# nucleum.net
KiCad netlist of a schematic drawn in EAGLE
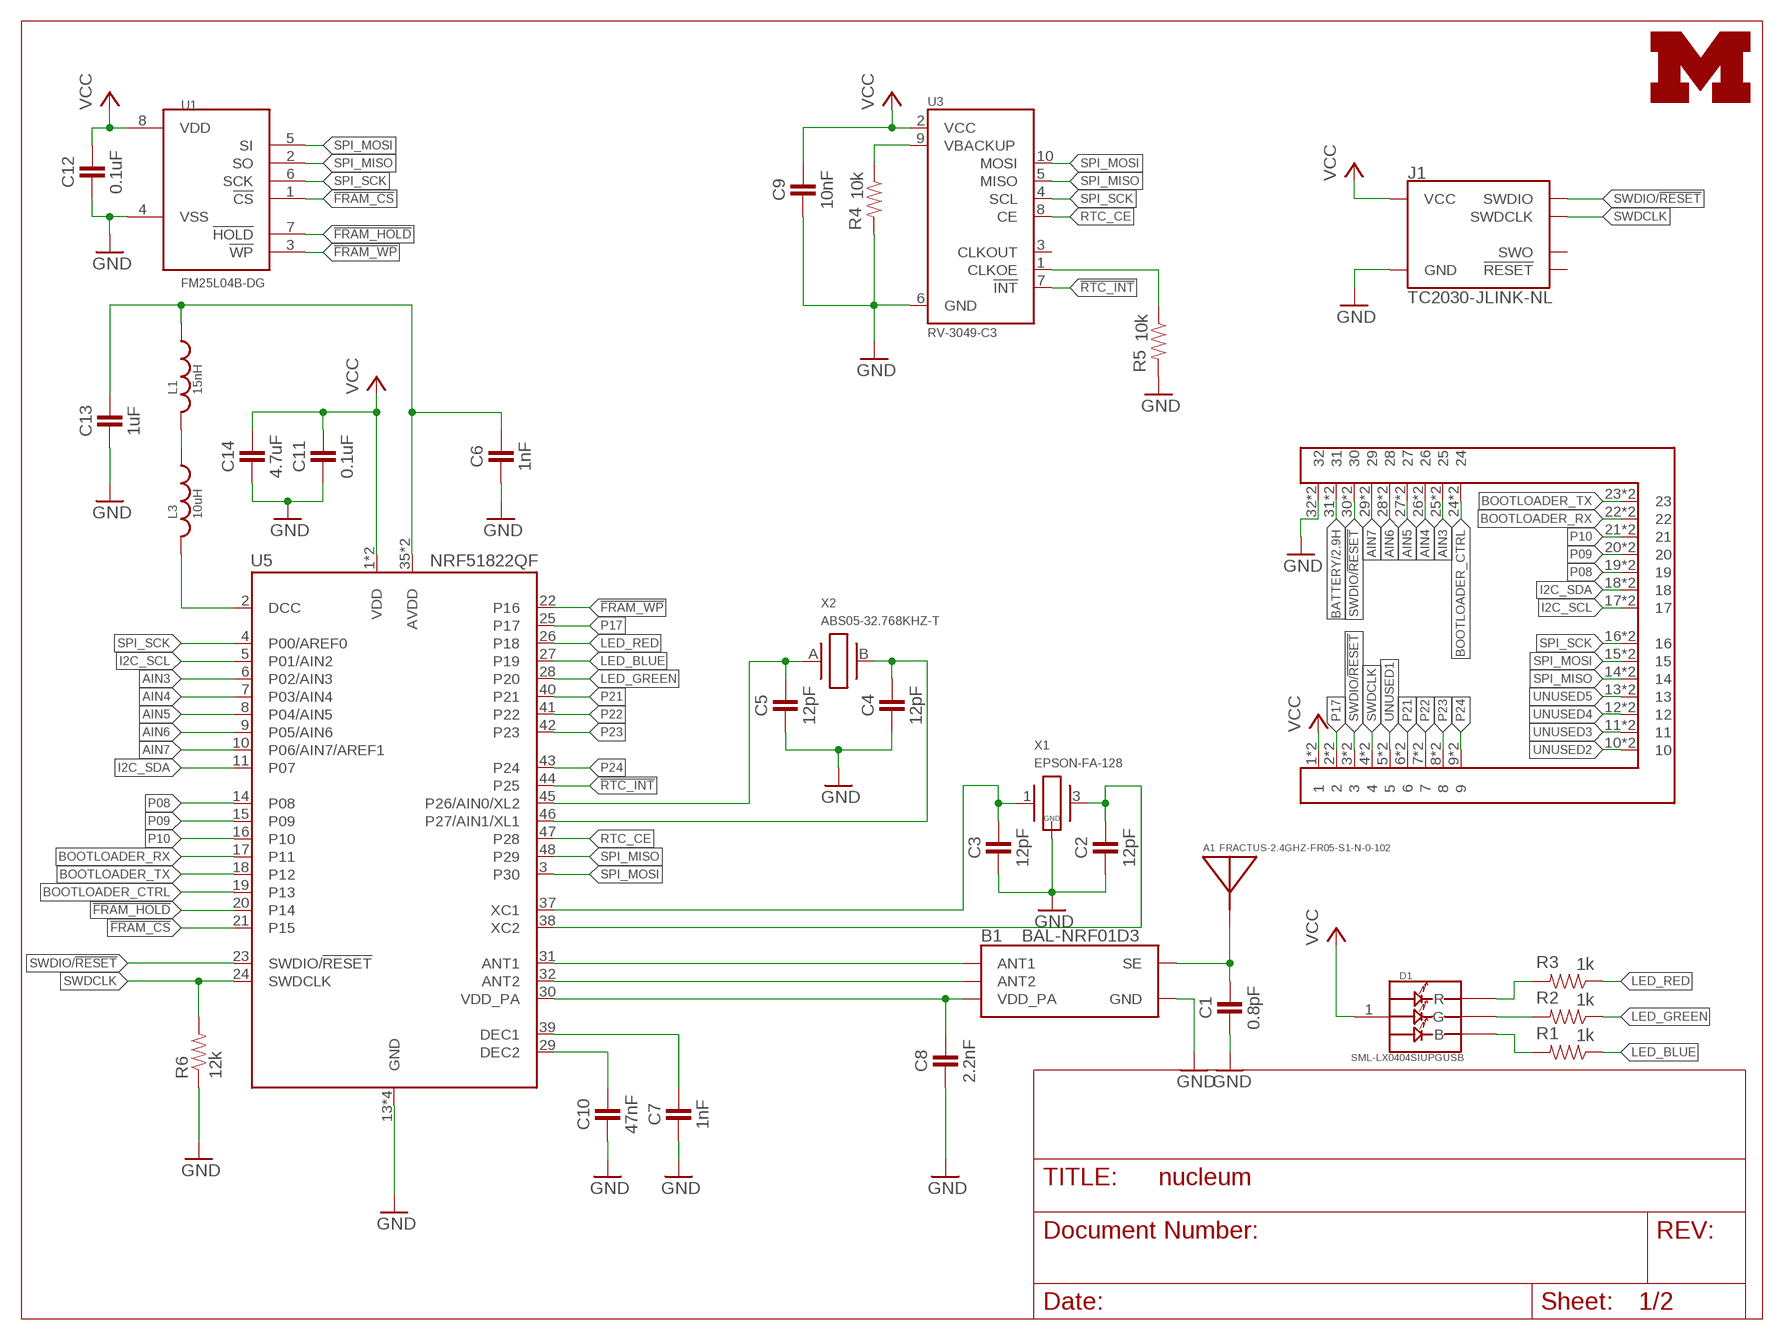
[diagram p0: schematic, sheet 1]
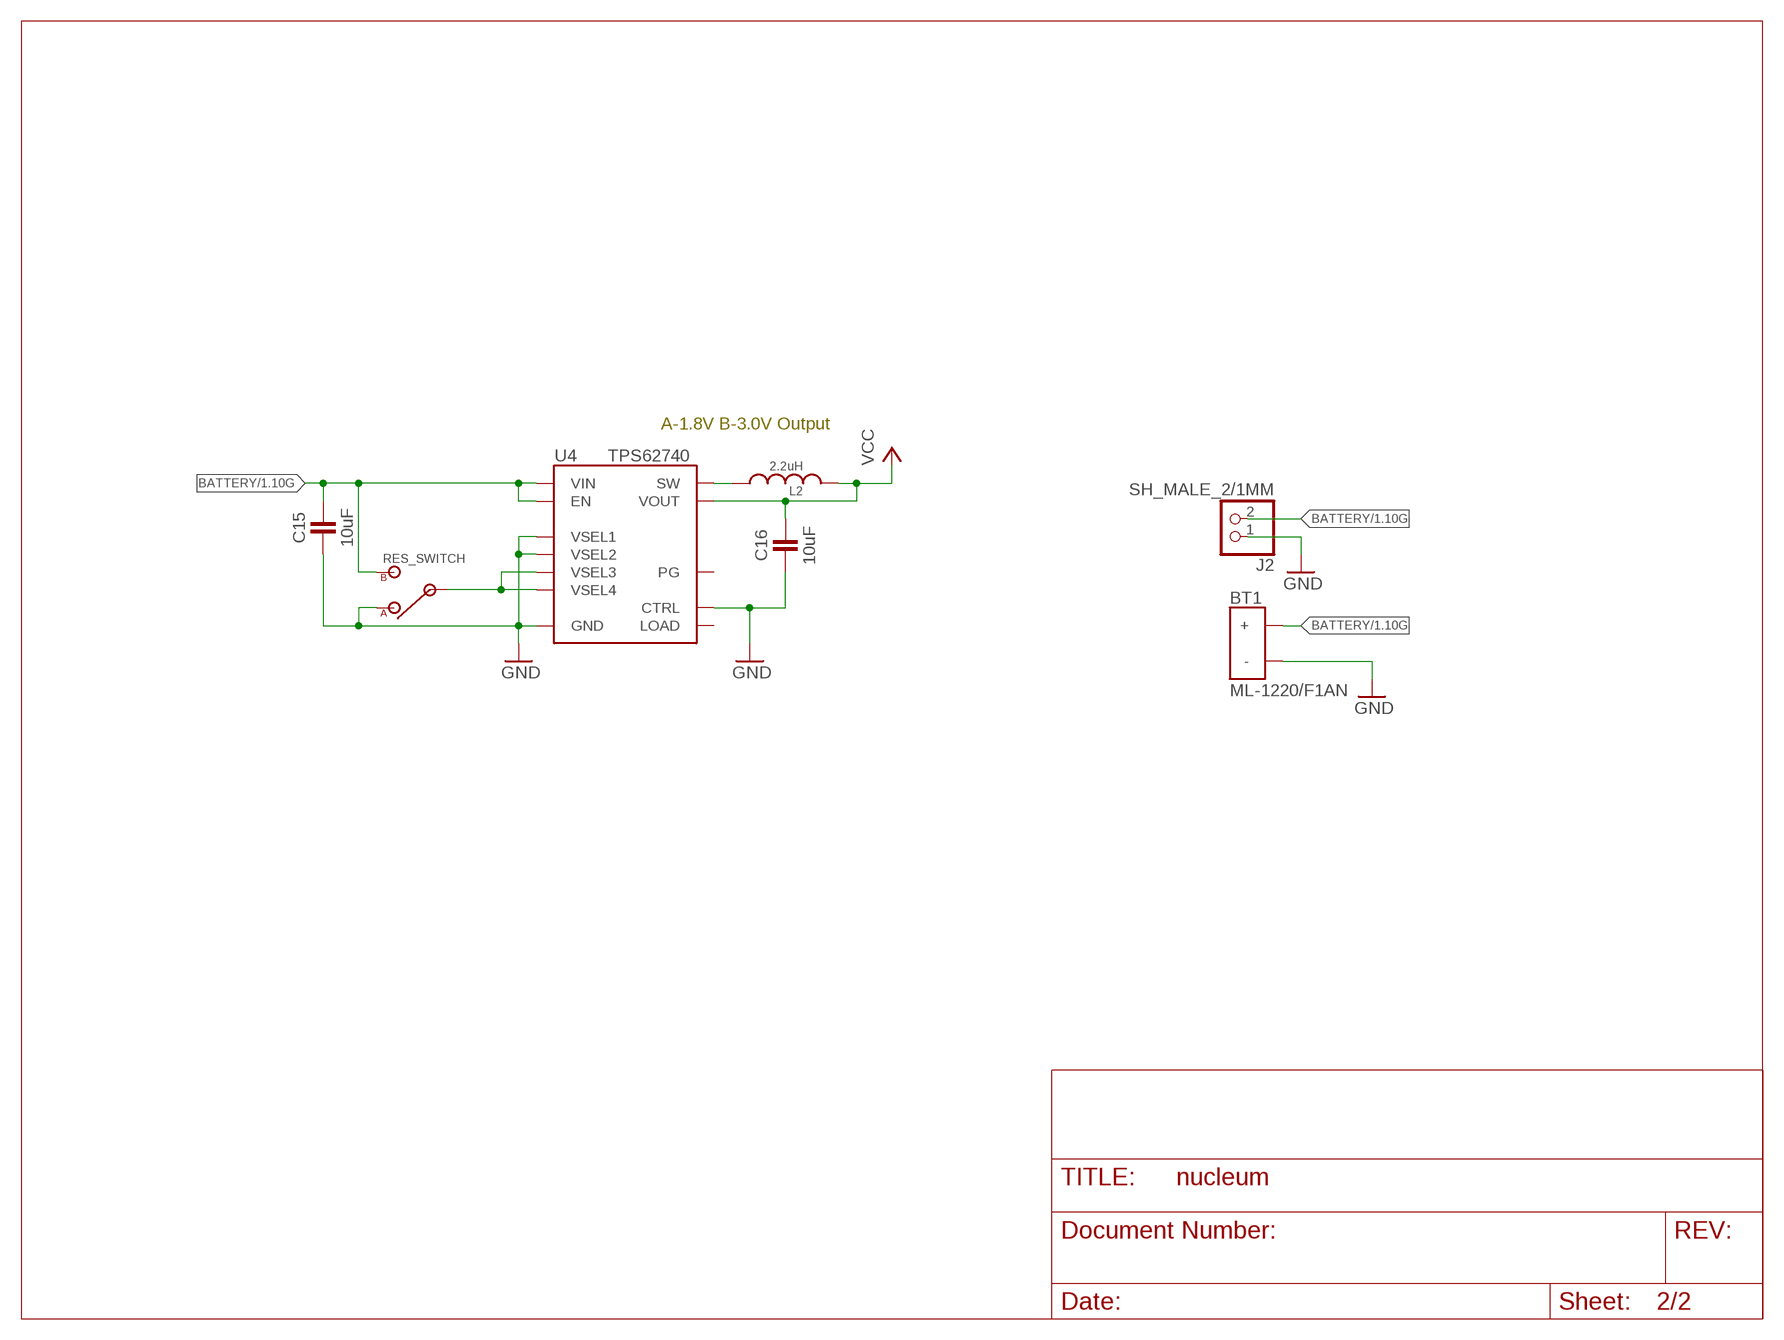
[diagram p1: schematic, sheet 2]

(export (version "E")
  (design (tool "Eeschema 10.0.6"))
  (components
    (comp (ref "BT1")
      (value "ML-1220/F1AN")
      (footprint "eagle-import:ML-1220_F1BN")
      (libsource (lib "eagle-import") (part "ML-1220/F1AN"))
    )
    (comp (ref "C15")
      (value "10uF")
      (footprint "eagle-import:0603_CAP")
      (libsource (lib "eagle-import") (part "CAPACITOR0603_CAP"))
    )
    (comp (ref "C16")
      (value "10uF")
      (footprint "eagle-import:0603_CAP")
      (libsource (lib "eagle-import") (part "CAPACITOR0603_CAP"))
    )
    (comp (ref "J2")
      (value "SH_MALE_2/1MM")
      (footprint "eagle-import:SH-1X2_1MM")
      (libsource (lib "eagle-import") (part "SH_MALE_2/1MM"))
    )
    (comp (ref "L2")
      (value "2.2uH")
      (footprint "eagle-import:MIPSZ201D")
      (libsource (lib "eagle-import") (part "MIPSZ2012D"))
    )
    (comp (ref "S1")
      (value "RES_SWITCH")
      (footprint "eagle-import:RES_SWITCH")
      (libsource (lib "eagle-import") (part "RES_SWITCH"))
    )
    (comp (ref "U4")
      (value "TPS62740")
      (footprint "eagle-import:R-PWSON-12")
      (libsource (lib "eagle-import") (part "TPS62740"))
    )
    (comp (ref "A1")
      (value "FRACTUS-2.4GHZ-FR05-S1-N-0-102")
      (footprint "eagle-import:FRACTUS-ANTENNA-FR05-S1-N-0-102")
      (libsource (lib "eagle-import") (part "FRACTUS-2.4GHZ-FR05-S1-N-0-102"))
    )
    (comp (ref "B1")
      (value "BAL-NRF01D3")
      (footprint "eagle-import:BAL-NRF01D3")
      (libsource (lib "eagle-import") (part "BAL-NRF01D3"))
    )
    (comp (ref "C1")
      (value "0.8pF")
      (footprint "eagle-import:0402_CAP")
      (libsource (lib "eagle-import") (part "CAPACITOR"))
    )
    (comp (ref "C2")
      (value "12pF")
      (footprint "eagle-import:0402_CAP")
      (libsource (lib "eagle-import") (part "CAPACITOR"))
    )
    (comp (ref "C3")
      (value "12pF")
      (footprint "eagle-import:0402_CAP")
      (libsource (lib "eagle-import") (part "CAPACITOR"))
    )
    (comp (ref "C4")
      (value "12pF")
      (footprint "eagle-import:0402_CAP")
      (libsource (lib "eagle-import") (part "CAPACITOR"))
    )
    (comp (ref "C5")
      (value "12pF")
      (footprint "eagle-import:0402_CAP")
      (libsource (lib "eagle-import") (part "CAPACITOR"))
    )
    (comp (ref "C6")
      (value "1nF")
      (footprint "eagle-import:0402_CAP")
      (libsource (lib "eagle-import") (part "CAPACITOR"))
    )
    (comp (ref "C7")
      (value "1nF")
      (footprint "eagle-import:0402_CAP")
      (libsource (lib "eagle-import") (part "CAPACITOR"))
    )
    (comp (ref "C8")
      (value "2.2nF")
      (footprint "eagle-import:0402_CAP")
      (libsource (lib "eagle-import") (part "CAPACITOR"))
    )
    (comp (ref "C9")
      (value "10nF")
      (footprint "eagle-import:0402_CAP")
      (libsource (lib "eagle-import") (part "CAPACITOR"))
    )
    (comp (ref "C10")
      (value "47nF")
      (footprint "eagle-import:0402_CAP")
      (libsource (lib "eagle-import") (part "CAPACITOR"))
    )
    (comp (ref "C11")
      (value "0.1uF")
      (footprint "eagle-import:0402_CAP")
      (libsource (lib "eagle-import") (part "CAPACITOR"))
    )
    (comp (ref "C12")
      (value "0.1uF")
      (footprint "eagle-import:0402_CAP")
      (libsource (lib "eagle-import") (part "CAPACITOR"))
    )
    (comp (ref "C13")
      (value "1uF")
      (footprint "eagle-import:0402_CAP")
      (libsource (lib "eagle-import") (part "CAPACITOR"))
    )
    (comp (ref "C14")
      (value "4.7uF")
      (footprint "eagle-import:0402_CAP")
      (libsource (lib "eagle-import") (part "CAPACITOR"))
    )
    (comp (ref "D1")
      (value "SML-LX0404SIUPGUSB")
      (footprint "eagle-import:1MM_SQ_4PAD")
      (libsource (lib "eagle-import") (part "SML-LX0404SIUPGUSB"))
    )
    (comp (ref "J1")
      (value "TC2030-JLINK-NL")
      (footprint "eagle-import:TC2030-IDC-NL")
      (libsource (lib "eagle-import") (part "TC2030-JLINK-NL"))
    )
    (comp (ref "J3")
      (value "ATUM-HEADER")
      (footprint "eagle-import:ATUM-HEADER")
      (libsource (lib "eagle-import") (part "ATUM-HEADER"))
    )
    (comp (ref "L1")
      (value "15nH")
      (footprint "eagle-import:0402_CAP")
      (libsource (lib "eagle-import") (part "INDUCTOR0402"))
    )
    (comp (ref "L3")
      (value "10uH")
      (footprint "eagle-import:0603_CAP")
      (libsource (lib "eagle-import") (part "INDUCTOR0603"))
    )
    (comp (ref "LOGO1")
      (value "UMICH_SOLID_TINY")
      (footprint "eagle-import:UMICH_SOLID_50MIL")
      (libsource (lib "eagle-import") (part "UMICH_SOLID_TINY"))
    )
    (comp (ref "R1")
      (value "1k")
      (footprint "eagle-import:0402_RES")
      (libsource (lib "eagle-import") (part "RESISTOR0402_RES"))
    )
    (comp (ref "R2")
      (value "1k")
      (footprint "eagle-import:0402_RES")
      (libsource (lib "eagle-import") (part "RESISTOR0402_RES"))
    )
    (comp (ref "R3")
      (value "1k")
      (footprint "eagle-import:0402_RES")
      (libsource (lib "eagle-import") (part "RESISTOR0402_RES"))
    )
    (comp (ref "R4")
      (value "10k")
      (footprint "eagle-import:0402_RES")
      (libsource (lib "eagle-import") (part "RESISTOR0402_RES"))
    )
    (comp (ref "R5")
      (value "10k")
      (footprint "eagle-import:0402_RES")
      (libsource (lib "eagle-import") (part "RESISTOR0402_RES"))
    )
    (comp (ref "R6")
      (value "12k")
      (footprint "eagle-import:0402_RES")
      (libsource (lib "eagle-import") (part "RESISTOR0402_RES"))
    )
    (comp (ref "U1")
      (value "FM25L04B-DG")
      (footprint "eagle-import:TDFN-8")
      (libsource (lib "eagle-import") (part "FM25L04B-DG"))
    )
    (comp (ref "U3")
      (value "RV-3049-C3")
      (footprint "eagle-import:MICRO-CRYSTAL-C3")
      (libsource (lib "eagle-import") (part "RV-3049-C3"))
    )
    (comp (ref "U5")
      (value "NRF51822QF")
      (footprint "eagle-import:QFN-48-6MM")
      (libsource (lib "eagle-import") (part "NRF51822QF"))
    )
    (comp (ref "X1")
      (value "EPSON-FA-128")
      (footprint "eagle-import:FA-128")
      (libsource (lib "eagle-import") (part "EPSON-FA-128"))
    )
    (comp (ref "X2")
      (value "ABS05-32.768KHZ-T")
      (footprint "eagle-import:ABS05")
      (libsource (lib "eagle-import") (part "ABS05-32.768KHZ-T"))
    )
  )
  (nets
    (net (code "1") (name "AIN3") (class "Default")
      (node (ref "J3") (pin "25") (pinfunction "25_25") (pintype "bidirectional"))
      (node (ref "J3") (pin "25B") (pinfunction "25_25B") (pintype "bidirectional"))
      (node (ref "U5") (pin "6") (pinfunction "P02/AIN3_6") (pintype "bidirectional"))
    )
    (net (code "2") (name "AIN4") (class "Default")
      (node (ref "J3") (pin "26") (pinfunction "26_26") (pintype "bidirectional"))
      (node (ref "J3") (pin "26B") (pinfunction "26_26B") (pintype "bidirectional"))
      (node (ref "U5") (pin "7") (pinfunction "P03/AIN4_7") (pintype "bidirectional"))
    )
    (net (code "3") (name "AIN5") (class "Default")
      (node (ref "J3") (pin "27") (pinfunction "27_27") (pintype "bidirectional"))
      (node (ref "J3") (pin "27B") (pinfunction "27_27B") (pintype "bidirectional"))
      (node (ref "U5") (pin "8") (pinfunction "P04/AIN5_8") (pintype "bidirectional"))
    )
    (net (code "4") (name "AIN6") (class "Default")
      (node (ref "J3") (pin "28") (pinfunction "28_28") (pintype "bidirectional"))
      (node (ref "J3") (pin "28B") (pinfunction "28_28B") (pintype "bidirectional"))
      (node (ref "U5") (pin "9") (pinfunction "P05/AIN6_9") (pintype "bidirectional"))
    )
    (net (code "5") (name "AIN7") (class "Default")
      (node (ref "J3") (pin "29") (pinfunction "29_29") (pintype "bidirectional"))
      (node (ref "J3") (pin "29B") (pinfunction "29_29B") (pintype "bidirectional"))
      (node (ref "U5") (pin "10") (pinfunction "P06/AIN7/AREF1_10") (pintype "bidirectional"))
    )
    (net (code "6") (name "BATTERY") (class "Default")
      (node (ref "BT1") (pin "POS") (pinfunction "+_POS") (pintype "bidirectional"))
      (node (ref "C15") (pin "1") (pinfunction "1_1") (pintype "bidirectional"))
      (node (ref "J2") (pin "2") (pinfunction "2_2") (pintype "passive"))
      (node (ref "J3") (pin "31") (pinfunction "31_31") (pintype "bidirectional"))
      (node (ref "J3") (pin "31B") (pinfunction "31_31B") (pintype "bidirectional"))
      (node (ref "S1") (pin "B") (pinfunction "B_B") (pintype "bidirectional"))
      (node (ref "U4") (pin "1") (pinfunction "VIN_1") (pintype "bidirectional"))
      (node (ref "U4") (pin "12") (pinfunction "EN_12") (pintype "bidirectional"))
    )
    (net (code "7") (name "BOOTLOADER_CTRL") (class "Default")
      (node (ref "J3") (pin "24") (pinfunction "24_24") (pintype "bidirectional"))
      (node (ref "J3") (pin "24B") (pinfunction "24_24B") (pintype "bidirectional"))
      (node (ref "U5") (pin "19") (pinfunction "P13_19") (pintype "bidirectional"))
    )
    (net (code "8") (name "BOOTLOADER_RX") (class "Default")
      (node (ref "J3") (pin "22") (pinfunction "22_22") (pintype "bidirectional"))
      (node (ref "J3") (pin "22B") (pinfunction "22_22B") (pintype "bidirectional"))
      (node (ref "U5") (pin "17") (pinfunction "P11_17") (pintype "bidirectional"))
    )
    (net (code "9") (name "BOOTLOADER_TX") (class "Default")
      (node (ref "J3") (pin "23") (pinfunction "23_23") (pintype "bidirectional"))
      (node (ref "J3") (pin "23B") (pinfunction "23_23B") (pintype "bidirectional"))
      (node (ref "U5") (pin "18") (pinfunction "P12_18") (pintype "bidirectional"))
    )
    (net (code "10") (name "GND") (class "Default")
      (node (ref "B1") (pin "GND") (pinfunction "GND_GND") (pintype "bidirectional"))
      (node (ref "BT1") (pin "NEG") (pinfunction "-_NEG") (pintype "bidirectional"))
      (node (ref "C1") (pin "2") (pinfunction "2_2") (pintype "bidirectional"))
      (node (ref "C10") (pin "2") (pinfunction "2_2") (pintype "bidirectional"))
      (node (ref "C11") (pin "2") (pinfunction "2_2") (pintype "bidirectional"))
      (node (ref "C12") (pin "2") (pinfunction "2_2") (pintype "bidirectional"))
      (node (ref "C13") (pin "2") (pinfunction "2_2") (pintype "bidirectional"))
      (node (ref "C14") (pin "2") (pinfunction "2_2") (pintype "bidirectional"))
      (node (ref "C15") (pin "2") (pinfunction "2_2") (pintype "bidirectional"))
      (node (ref "C16") (pin "2") (pinfunction "2_2") (pintype "bidirectional"))
      (node (ref "C2") (pin "2") (pinfunction "2_2") (pintype "bidirectional"))
      (node (ref "C3") (pin "2") (pinfunction "2_2") (pintype "bidirectional"))
      (node (ref "C4") (pin "2") (pinfunction "2_2") (pintype "bidirectional"))
      (node (ref "C5") (pin "2") (pinfunction "2_2") (pintype "bidirectional"))
      (node (ref "C6") (pin "2") (pinfunction "2_2") (pintype "bidirectional"))
      (node (ref "C7") (pin "2") (pinfunction "2_2") (pintype "bidirectional"))
      (node (ref "C8") (pin "2") (pinfunction "2_2") (pintype "bidirectional"))
      (node (ref "C9") (pin "2") (pinfunction "2_2") (pintype "bidirectional"))
      (node (ref "J1") (pin "5") (pinfunction "GND_5") (pintype "bidirectional"))
      (node (ref "J2") (pin "1") (pinfunction "1_1") (pintype "passive"))
      (node (ref "J3") (pin "32") (pinfunction "32_32") (pintype "bidirectional"))
      (node (ref "J3") (pin "32B") (pinfunction "32_32B") (pintype "bidirectional"))
      (node (ref "R4") (pin "2") (pinfunction "2_2") (pintype "passive"))
      (node (ref "R5") (pin "2") (pinfunction "2_2") (pintype "passive"))
      (node (ref "R6") (pin "1") (pinfunction "1_1") (pintype "passive"))
      (node (ref "S1") (pin "A") (pinfunction "A_A") (pintype "bidirectional"))
      (node (ref "U1") (pin "4") (pinfunction "VSS_4") (pintype "bidirectional"))
      (node (ref "U3") (pin "6") (pinfunction "GND_6") (pintype "bidirectional"))
      (node (ref "U4") (pin "10") (pinfunction "VSEL2_10") (pintype "bidirectional"))
      (node (ref "U4") (pin "11") (pinfunction "VSEL1_11") (pintype "bidirectional"))
      (node (ref "U4") (pin "3") (pinfunction "GND_3") (pintype "bidirectional"))
      (node (ref "U4") (pin "4") (pinfunction "CTRL_4") (pintype "bidirectional"))
      (node (ref "U4") (pin "NC") (pinfunction "GND_NC") (pintype "bidirectional"))
      (node (ref "U5") (pin "13") (pinfunction "GND_13") (pintype "bidirectional"))
      (node (ref "U5") (pin "33") (pinfunction "GND_33") (pintype "bidirectional"))
      (node (ref "U5") (pin "34") (pinfunction "GND_34") (pintype "bidirectional"))
      (node (ref "U5") (pin "GND") (pinfunction "GND_GND") (pintype "bidirectional"))
      (node (ref "X1") (pin "2") (pinfunction "GND_2") (pintype "bidirectional"))
      (node (ref "X1") (pin "4") (pinfunction "GND_4") (pintype "bidirectional"))
    )
    (net (code "11") (name "I2C_SCL") (class "Default")
      (node (ref "J3") (pin "17") (pinfunction "17_17") (pintype "bidirectional"))
      (node (ref "J3") (pin "17B") (pinfunction "17_17B") (pintype "bidirectional"))
      (node (ref "U5") (pin "5") (pinfunction "P01/AIN2_5") (pintype "bidirectional"))
    )
    (net (code "12") (name "I2C_SDA") (class "Default")
      (node (ref "J3") (pin "18") (pinfunction "18_18") (pintype "bidirectional"))
      (node (ref "J3") (pin "18B") (pinfunction "18_18B") (pintype "bidirectional"))
      (node (ref "U5") (pin "11") (pinfunction "P07_11") (pintype "bidirectional"))
    )
    (net (code "13") (name "LED_BLUE") (class "Default")
      (node (ref "R1") (pin "1") (pinfunction "1_1") (pintype "passive"))
      (node (ref "U5") (pin "27") (pinfunction "P19_27") (pintype "bidirectional"))
    )
    (net (code "14") (name "LED_GREEN") (class "Default")
      (node (ref "R2") (pin "1") (pinfunction "1_1") (pintype "passive"))
      (node (ref "U5") (pin "28") (pinfunction "P20_28") (pintype "bidirectional"))
    )
    (net (code "15") (name "LED_RED") (class "Default")
      (node (ref "R3") (pin "1") (pinfunction "1_1") (pintype "passive"))
      (node (ref "U5") (pin "26") (pinfunction "P18_26") (pintype "bidirectional"))
    )
    (net (code "16") (name "Net-(A1-ANTENNA)") (class "Default")
      (node (ref "A1") (pin "1") (pinfunction "ANTENNA_1") (pintype "bidirectional"))
      (node (ref "B1") (pin "SE") (pinfunction "SE_SE") (pintype "bidirectional"))
      (node (ref "C1") (pin "1") (pinfunction "1_1") (pintype "bidirectional"))
    )
    (net (code "17") (name "Net-(B1-VDD_PA)") (class "Default")
      (node (ref "B1") (pin "VCC") (pinfunction "VDD_PA_VCC") (pintype "bidirectional"))
      (node (ref "C8") (pin "1") (pinfunction "1_1") (pintype "bidirectional"))
      (node (ref "U5") (pin "30") (pinfunction "VDD_PA_30") (pintype "bidirectional"))
    )
    (net (code "18") (name "Net-(C13-Pad1)") (class "Default")
      (node (ref "C13") (pin "1") (pinfunction "1_1") (pintype "bidirectional"))
      (node (ref "C6") (pin "1") (pinfunction "1_1") (pintype "bidirectional"))
      (node (ref "L1") (pin "1") (pinfunction "1_1") (pintype "bidirectional"))
      (node (ref "U5") (pin "35") (pinfunction "AVDD_35") (pintype "bidirectional"))
      (node (ref "U5") (pin "36") (pinfunction "AVDD_36") (pintype "bidirectional"))
    )
    (net (code "19") (name "Net-(D1-B)") (class "Default")
      (node (ref "D1") (pin "3") (pinfunction "B_3") (pintype "output"))
      (node (ref "R1") (pin "2") (pinfunction "2_2") (pintype "passive"))
    )
    (net (code "20") (name "Net-(D1-G)") (class "Default")
      (node (ref "D1") (pin "4") (pinfunction "G_4") (pintype "output"))
      (node (ref "R2") (pin "2") (pinfunction "2_2") (pintype "passive"))
    )
    (net (code "21") (name "Net-(D1-R)") (class "Default")
      (node (ref "D1") (pin "2") (pinfunction "R_2") (pintype "output"))
      (node (ref "R3") (pin "2") (pinfunction "2_2") (pintype "passive"))
    )
    (net (code "22") (name "Net-(L1-Pad2)") (class "Default")
      (node (ref "L1") (pin "2") (pinfunction "2_2") (pintype "bidirectional"))
      (node (ref "L3") (pin "1") (pinfunction "1_1") (pintype "bidirectional"))
    )
    (net (code "23") (name "Net-(S1-IN)") (class "Default")
      (node (ref "S1") (pin "C") (pinfunction "IN_C") (pintype "bidirectional"))
      (node (ref "U4") (pin "8") (pinfunction "VSEL4_8") (pintype "bidirectional"))
      (node (ref "U4") (pin "9") (pinfunction "VSEL3_9") (pintype "bidirectional"))
    )
    (net (code "24") (name "Net-(U3-CLKOE)") (class "Default")
      (node (ref "R5") (pin "1") (pinfunction "1_1") (pintype "passive"))
      (node (ref "U3") (pin "1") (pinfunction "CLKOE_1") (pintype "bidirectional"))
    )
    (net (code "25") (name "Net-(U3-VBACKUP)") (class "Default")
      (node (ref "R4") (pin "1") (pinfunction "1_1") (pintype "passive"))
      (node (ref "U3") (pin "9") (pinfunction "VBACKUP_9") (pintype "bidirectional"))
    )
    (net (code "26") (name "Net-(U4-SW)") (class "Default")
      (node (ref "L2") (pin "1") (pinfunction "1_1") (pintype "bidirectional"))
      (node (ref "U4") (pin "2") (pinfunction "SW_2") (pintype "bidirectional"))
    )
    (net (code "27") (name "Net-(U5-ANT1)") (class "Default")
      (node (ref "B1") (pin "ANT1") (pinfunction "ANT1_ANT1") (pintype "bidirectional"))
      (node (ref "U5") (pin "31") (pinfunction "ANT1_31") (pintype "bidirectional"))
    )
    (net (code "28") (name "Net-(U5-ANT2)") (class "Default")
      (node (ref "B1") (pin "ANT2") (pinfunction "ANT2_ANT2") (pintype "bidirectional"))
      (node (ref "U5") (pin "32") (pinfunction "ANT2_32") (pintype "bidirectional"))
    )
    (net (code "29") (name "Net-(U5-DCC)") (class "Default")
      (node (ref "L3") (pin "2") (pinfunction "2_2") (pintype "bidirectional"))
      (node (ref "U5") (pin "2") (pinfunction "DCC_2") (pintype "bidirectional"))
    )
    (net (code "30") (name "Net-(U5-DEC1)") (class "Default")
      (node (ref "C7") (pin "1") (pinfunction "1_1") (pintype "bidirectional"))
      (node (ref "U5") (pin "39") (pinfunction "DEC1_39") (pintype "bidirectional"))
    )
    (net (code "31") (name "Net-(U5-DEC2)") (class "Default")
      (node (ref "C10") (pin "1") (pinfunction "1_1") (pintype "bidirectional"))
      (node (ref "U5") (pin "29") (pinfunction "DEC2_29") (pintype "bidirectional"))
    )
    (net (code "32") (name "Net-(U5-P26{slash}AIN0{slash}XL2)") (class "Default")
      (node (ref "C5") (pin "1") (pinfunction "1_1") (pintype "bidirectional"))
      (node (ref "U5") (pin "45") (pinfunction "P26/AIN0/XL2_45") (pintype "bidirectional"))
      (node (ref "X2") (pin "A") (pinfunction "1_A") (pintype "bidirectional"))
    )
    (net (code "33") (name "Net-(U5-P27{slash}AIN1{slash}XL1)") (class "Default")
      (node (ref "C4") (pin "1") (pinfunction "1_1") (pintype "bidirectional"))
      (node (ref "U5") (pin "46") (pinfunction "P27/AIN1/XL1_46") (pintype "bidirectional"))
      (node (ref "X2") (pin "B") (pinfunction "2_B") (pintype "bidirectional"))
    )
    (net (code "34") (name "Net-(U5-XC1)") (class "Default")
      (node (ref "C3") (pin "1") (pinfunction "1_1") (pintype "bidirectional"))
      (node (ref "U5") (pin "37") (pinfunction "XC1_37") (pintype "bidirectional"))
      (node (ref "X1") (pin "1") (pinfunction "1_1") (pintype "bidirectional"))
    )
    (net (code "35") (name "Net-(U5-XC2)") (class "Default")
      (node (ref "C2") (pin "1") (pinfunction "1_1") (pintype "bidirectional"))
      (node (ref "U5") (pin "38") (pinfunction "XC2_38") (pintype "bidirectional"))
      (node (ref "X1") (pin "3") (pinfunction "2_3") (pintype "bidirectional"))
    )
    (net (code "36") (name "P08") (class "Default")
      (node (ref "J3") (pin "19") (pinfunction "19_19") (pintype "bidirectional"))
      (node (ref "J3") (pin "19B") (pinfunction "19_19B") (pintype "bidirectional"))
      (node (ref "U5") (pin "14") (pinfunction "P08_14") (pintype "bidirectional"))
    )
    (net (code "37") (name "P09") (class "Default")
      (node (ref "J3") (pin "20") (pinfunction "20_20") (pintype "bidirectional"))
      (node (ref "J3") (pin "20B") (pinfunction "20_20B") (pintype "bidirectional"))
      (node (ref "U5") (pin "15") (pinfunction "P09_15") (pintype "bidirectional"))
    )
    (net (code "38") (name "P10") (class "Default")
      (node (ref "J3") (pin "21") (pinfunction "21_21") (pintype "bidirectional"))
      (node (ref "J3") (pin "21B") (pinfunction "21_21B") (pintype "bidirectional"))
      (node (ref "U5") (pin "16") (pinfunction "P10_16") (pintype "bidirectional"))
    )
    (net (code "39") (name "P17") (class "Default")
      (node (ref "J3") (pin "2") (pinfunction "2_2") (pintype "bidirectional"))
      (node (ref "J3") (pin "2B") (pinfunction "2_2B") (pintype "bidirectional"))
      (node (ref "U5") (pin "25") (pinfunction "P17_25") (pintype "bidirectional"))
    )
    (net (code "40") (name "P21") (class "Default")
      (node (ref "J3") (pin "6") (pinfunction "6_6") (pintype "bidirectional"))
      (node (ref "J3") (pin "6B") (pinfunction "6_6B") (pintype "bidirectional"))
      (node (ref "U5") (pin "40") (pinfunction "P21_40") (pintype "bidirectional"))
    )
    (net (code "41") (name "P22") (class "Default")
      (node (ref "J3") (pin "7") (pinfunction "7_7") (pintype "bidirectional"))
      (node (ref "J3") (pin "7B") (pinfunction "7_7B") (pintype "bidirectional"))
      (node (ref "U5") (pin "41") (pinfunction "P22_41") (pintype "bidirectional"))
    )
    (net (code "42") (name "P23") (class "Default")
      (node (ref "J3") (pin "8") (pinfunction "8_8") (pintype "bidirectional"))
      (node (ref "J3") (pin "8B") (pinfunction "8_8B") (pintype "bidirectional"))
      (node (ref "U5") (pin "42") (pinfunction "P23_42") (pintype "bidirectional"))
    )
    (net (code "43") (name "P24") (class "Default")
      (node (ref "J3") (pin "9") (pinfunction "9_9") (pintype "bidirectional"))
      (node (ref "J3") (pin "9B") (pinfunction "9_9B") (pintype "bidirectional"))
      (node (ref "U5") (pin "43") (pinfunction "P24_43") (pintype "bidirectional"))
    )
    (net (code "44") (name "RTC_CE") (class "Default")
      (node (ref "U3") (pin "8") (pinfunction "CE_8") (pintype "bidirectional"))
      (node (ref "U5") (pin "47") (pinfunction "P28_47") (pintype "bidirectional"))
    )
    (net (code "45") (name "SPI_MISO") (class "Default")
      (node (ref "J3") (pin "14") (pinfunction "14_14") (pintype "bidirectional"))
      (node (ref "J3") (pin "14B") (pinfunction "14_14B") (pintype "bidirectional"))
      (node (ref "U1") (pin "2") (pinfunction "SO_2") (pintype "bidirectional"))
      (node (ref "U3") (pin "5") (pinfunction "MISO_5") (pintype "bidirectional"))
      (node (ref "U5") (pin "48") (pinfunction "P29_48") (pintype "bidirectional"))
    )
    (net (code "46") (name "SPI_MOSI") (class "Default")
      (node (ref "J3") (pin "15") (pinfunction "15_15") (pintype "bidirectional"))
      (node (ref "J3") (pin "15B") (pinfunction "15_15B") (pintype "bidirectional"))
      (node (ref "U1") (pin "5") (pinfunction "SI_5") (pintype "bidirectional"))
      (node (ref "U3") (pin "10") (pinfunction "MOSI_10") (pintype "bidirectional"))
      (node (ref "U5") (pin "3") (pinfunction "P30_3") (pintype "bidirectional"))
    )
    (net (code "47") (name "SPI_SCK") (class "Default")
      (node (ref "J3") (pin "16") (pinfunction "16_16") (pintype "bidirectional"))
      (node (ref "J3") (pin "16B") (pinfunction "16_16B") (pintype "bidirectional"))
      (node (ref "U1") (pin "6") (pinfunction "SCK_6") (pintype "bidirectional"))
      (node (ref "U3") (pin "4") (pinfunction "SCL_4") (pintype "bidirectional"))
      (node (ref "U5") (pin "4") (pinfunction "P00/AREF0_4") (pintype "bidirectional"))
    )
    (net (code "48") (name "SWDCLK") (class "Default")
      (node (ref "J1") (pin "4") (pinfunction "SWDCLK_4") (pintype "bidirectional"))
      (node (ref "J3") (pin "4") (pinfunction "4_4") (pintype "bidirectional"))
      (node (ref "J3") (pin "4B") (pinfunction "4_4B") (pintype "bidirectional"))
      (node (ref "R6") (pin "2") (pinfunction "2_2") (pintype "passive"))
      (node (ref "U5") (pin "24") (pinfunction "SWDCLK_24") (pintype "bidirectional"))
    )
    (net (code "49") (name "SWDIO{slash}~{RESET}") (class "Default")
      (node (ref "J1") (pin "2") (pinfunction "SWDIO_2") (pintype "bidirectional"))
      (node (ref "J3") (pin "3") (pinfunction "3_3") (pintype "bidirectional"))
      (node (ref "J3") (pin "30") (pinfunction "30_30") (pintype "bidirectional"))
      (node (ref "J3") (pin "30B") (pinfunction "30_30B") (pintype "bidirectional"))
      (node (ref "J3") (pin "3B") (pinfunction "3_3B") (pintype "bidirectional"))
      (node (ref "U5") (pin "23") (pinfunction "SWDIO/~{RESET}_23") (pintype "bidirectional"))
    )
    (net (code "50") (name "UNUSED1") (class "Default")
      (node (ref "J3") (pin "5") (pinfunction "5_5") (pintype "bidirectional"))
      (node (ref "J3") (pin "5B") (pinfunction "5_5B") (pintype "bidirectional"))
    )
    (net (code "51") (name "UNUSED2") (class "Default")
      (node (ref "J3") (pin "10") (pinfunction "10_10") (pintype "bidirectional"))
      (node (ref "J3") (pin "10B") (pinfunction "10_10B") (pintype "bidirectional"))
    )
    (net (code "52") (name "UNUSED3") (class "Default")
      (node (ref "J3") (pin "11") (pinfunction "11_11") (pintype "bidirectional"))
      (node (ref "J3") (pin "11B") (pinfunction "11_11B") (pintype "bidirectional"))
    )
    (net (code "53") (name "UNUSED4") (class "Default")
      (node (ref "J3") (pin "12") (pinfunction "12_12") (pintype "bidirectional"))
      (node (ref "J3") (pin "12B") (pinfunction "12_12B") (pintype "bidirectional"))
    )
    (net (code "54") (name "UNUSED5") (class "Default")
      (node (ref "J3") (pin "13") (pinfunction "13_13") (pintype "bidirectional"))
      (node (ref "J3") (pin "13B") (pinfunction "13_13B") (pintype "bidirectional"))
    )
    (net (code "55") (name "VCC") (class "Default")
      (node (ref "C11") (pin "1") (pinfunction "1_1") (pintype "bidirectional"))
      (node (ref "C12") (pin "1") (pinfunction "1_1") (pintype "bidirectional"))
      (node (ref "C14") (pin "1") (pinfunction "1_1") (pintype "bidirectional"))
      (node (ref "C16") (pin "1") (pinfunction "1_1") (pintype "bidirectional"))
      (node (ref "C9") (pin "1") (pinfunction "1_1") (pintype "bidirectional"))
      (node (ref "D1") (pin "1") (pinfunction "VDD_1") (pintype "bidirectional"))
      (node (ref "J1") (pin "1") (pinfunction "VCC_1") (pintype "bidirectional"))
      (node (ref "J3") (pin "1") (pinfunction "1_1") (pintype "bidirectional"))
      (node (ref "J3") (pin "1B") (pinfunction "1_1B") (pintype "bidirectional"))
      (node (ref "L2") (pin "2") (pinfunction "2_2") (pintype "bidirectional"))
      (node (ref "U1") (pin "8") (pinfunction "VDD_8") (pintype "bidirectional"))
      (node (ref "U3") (pin "2") (pinfunction "VCC_2") (pintype "bidirectional"))
      (node (ref "U4") (pin "5") (pinfunction "VOUT_5") (pintype "bidirectional"))
      (node (ref "U5") (pin "1") (pinfunction "VDD_1") (pintype "bidirectional"))
      (node (ref "U5") (pin "12") (pinfunction "VDD_12") (pintype "bidirectional"))
    )
    (net (code "56") (name "unconnected-(J1-SWO-Pad6)") (class "Default")
      (node (ref "J1") (pin "6") (pinfunction "SWO_6") (pintype "bidirectional"))
    )
    (net (code "57") (name "unconnected-(J1-~{RESET}-Pad3)") (class "Default")
      (node (ref "J1") (pin "3") (pinfunction "~{RESET}_3") (pintype "bidirectional"))
    )
    (net (code "58") (name "unconnected-(U3-CLKOUT-Pad3)") (class "Default")
      (node (ref "U3") (pin "3") (pinfunction "CLKOUT_3") (pintype "bidirectional"))
    )
    (net (code "59") (name "unconnected-(U4-LOAD-Pad6)") (class "Default")
      (node (ref "U4") (pin "6") (pinfunction "LOAD_6") (pintype "bidirectional"))
    )
    (net (code "60") (name "unconnected-(U4-PG-Pad7)") (class "Default")
      (node (ref "U4") (pin "7") (pinfunction "PG_7") (pintype "bidirectional"))
    )
    (net (code "61") (name "~{FRAM_CS}") (class "Default")
      (node (ref "U1") (pin "1") (pinfunction "~{CS}_1") (pintype "bidirectional"))
      (node (ref "U5") (pin "21") (pinfunction "P15_21") (pintype "bidirectional"))
    )
    (net (code "62") (name "~{FRAM_HOLD}") (class "Default")
      (node (ref "U1") (pin "7") (pinfunction "~{HOLD}_7") (pintype "bidirectional"))
      (node (ref "U5") (pin "20") (pinfunction "P14_20") (pintype "bidirectional"))
    )
    (net (code "63") (name "~{FRAM_WP}") (class "Default")
      (node (ref "U1") (pin "3") (pinfunction "~{WP}_3") (pintype "bidirectional"))
      (node (ref "U5") (pin "22") (pinfunction "P16_22") (pintype "bidirectional"))
    )
    (net (code "64") (name "~{RTC_INT}") (class "Default")
      (node (ref "U3") (pin "7") (pinfunction "~{INT}_7") (pintype "bidirectional"))
      (node (ref "U5") (pin "44") (pinfunction "P25_44") (pintype "bidirectional"))
    )
  )
)
